# MTB-v2_0_0.net
KiCad netlist of a schematic drawn in EAGLE
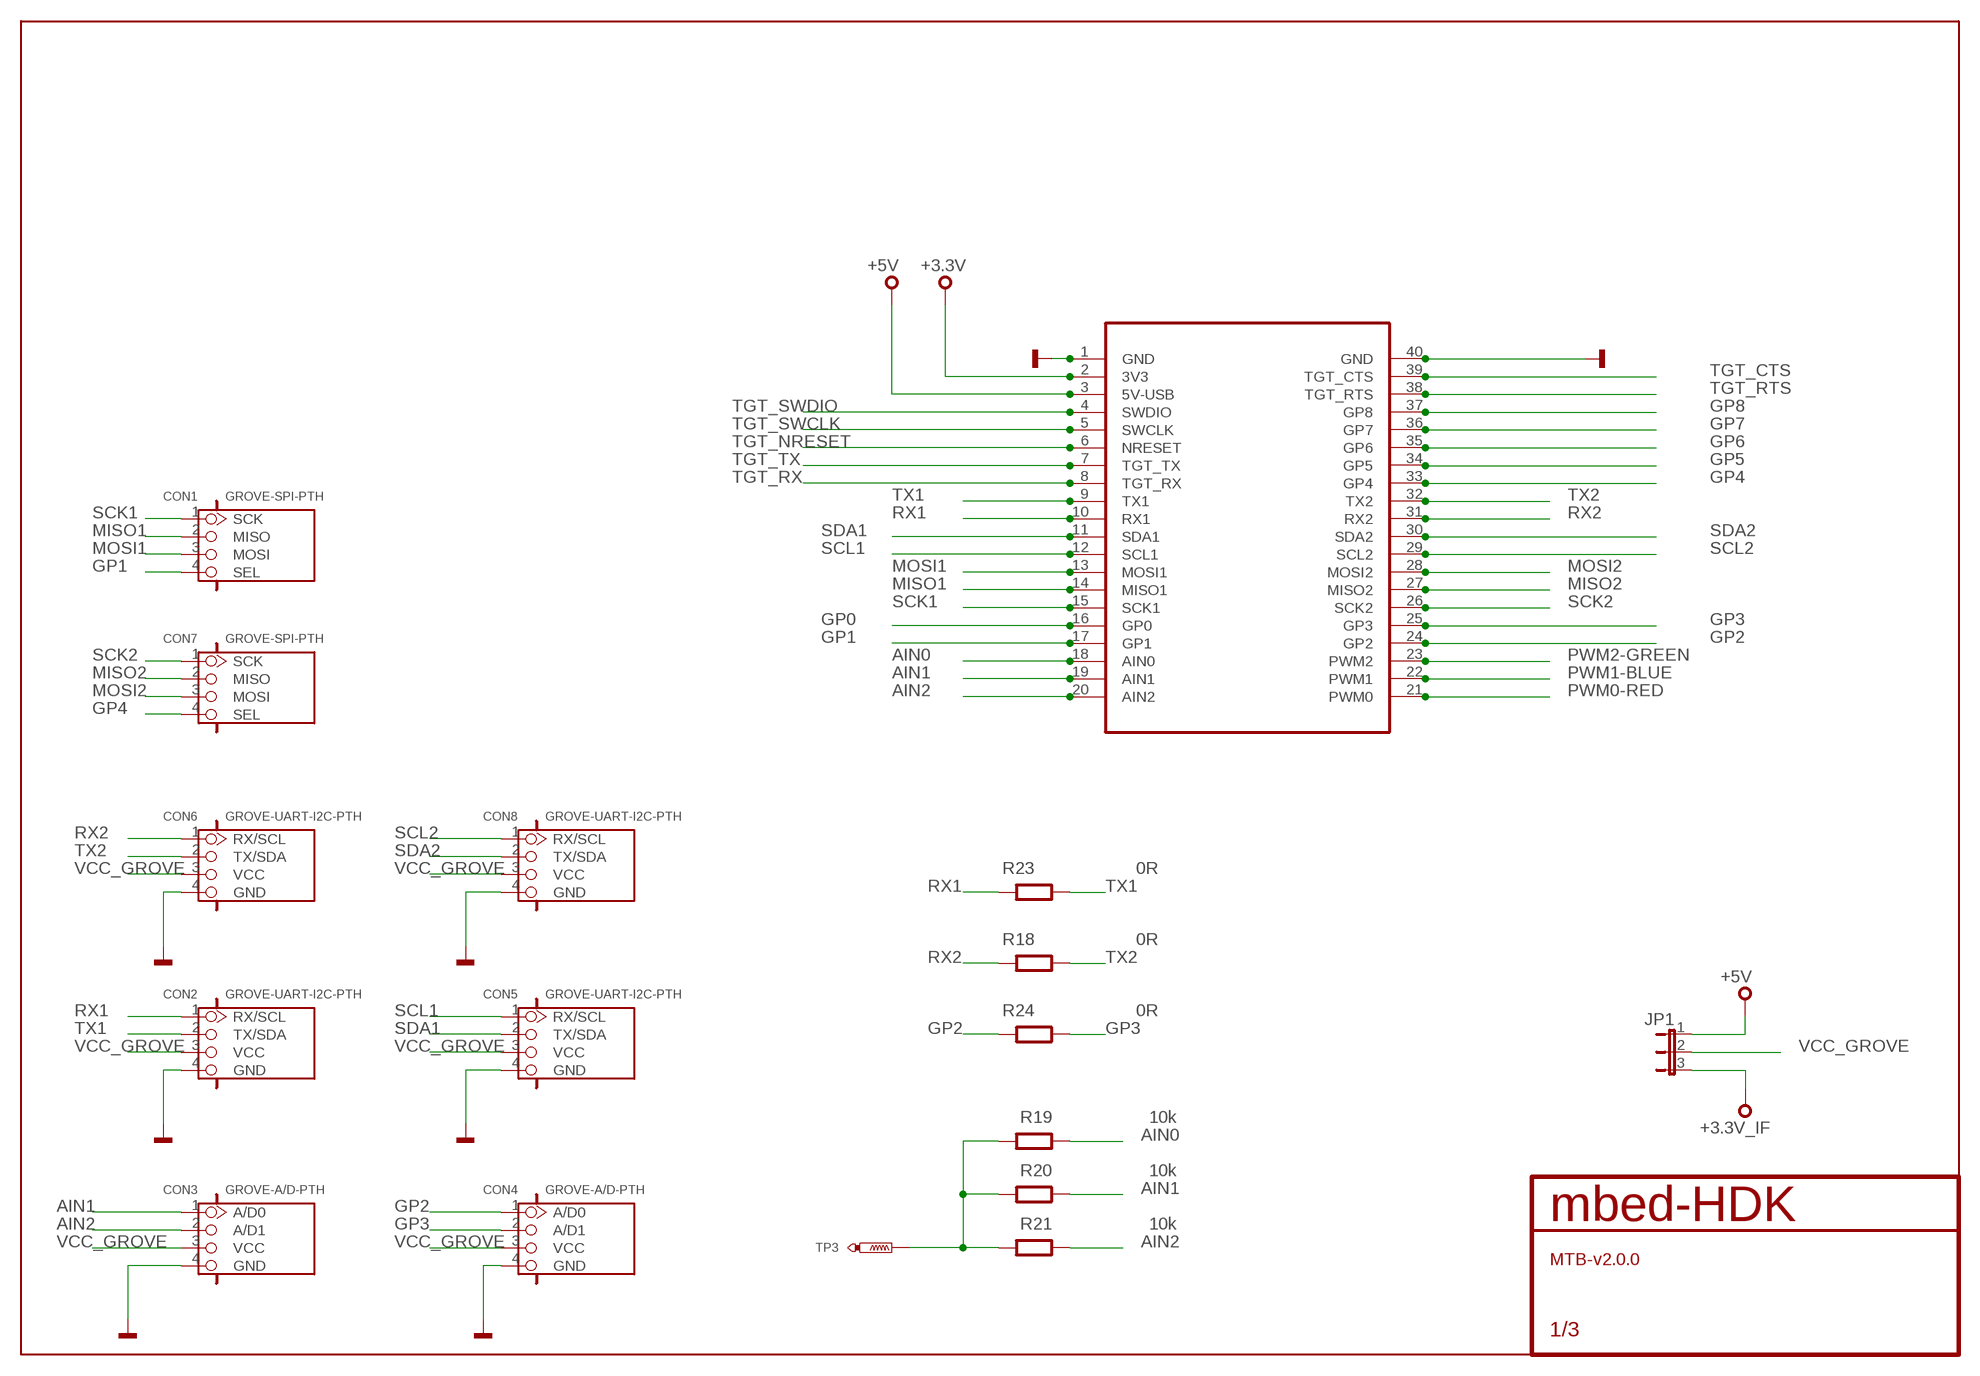
[diagram p0: schematic, sheet 1]
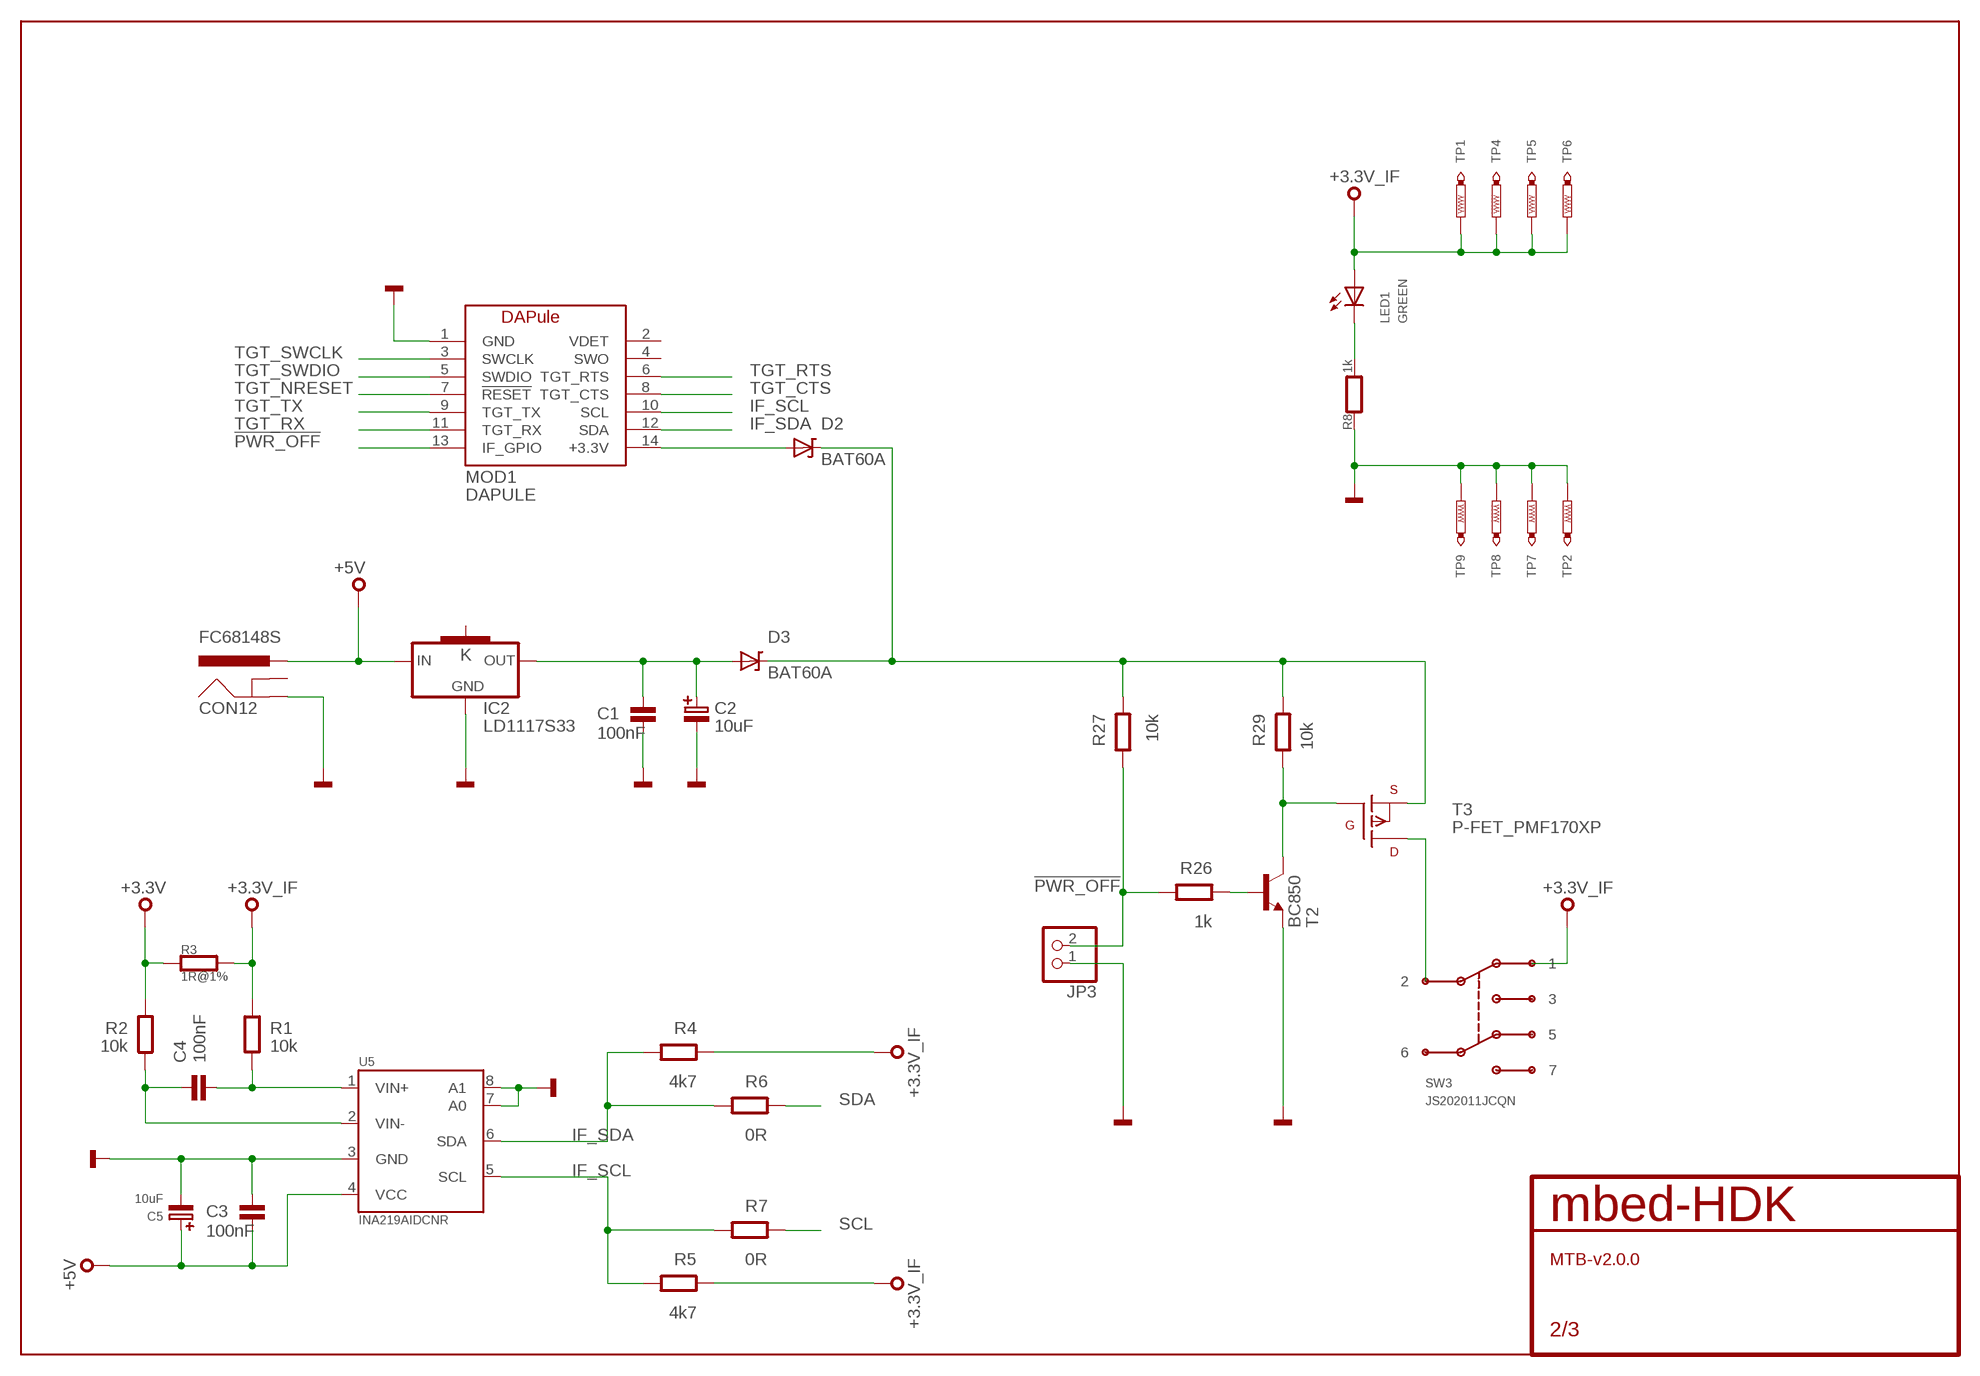
[diagram p1: schematic, sheet 2]
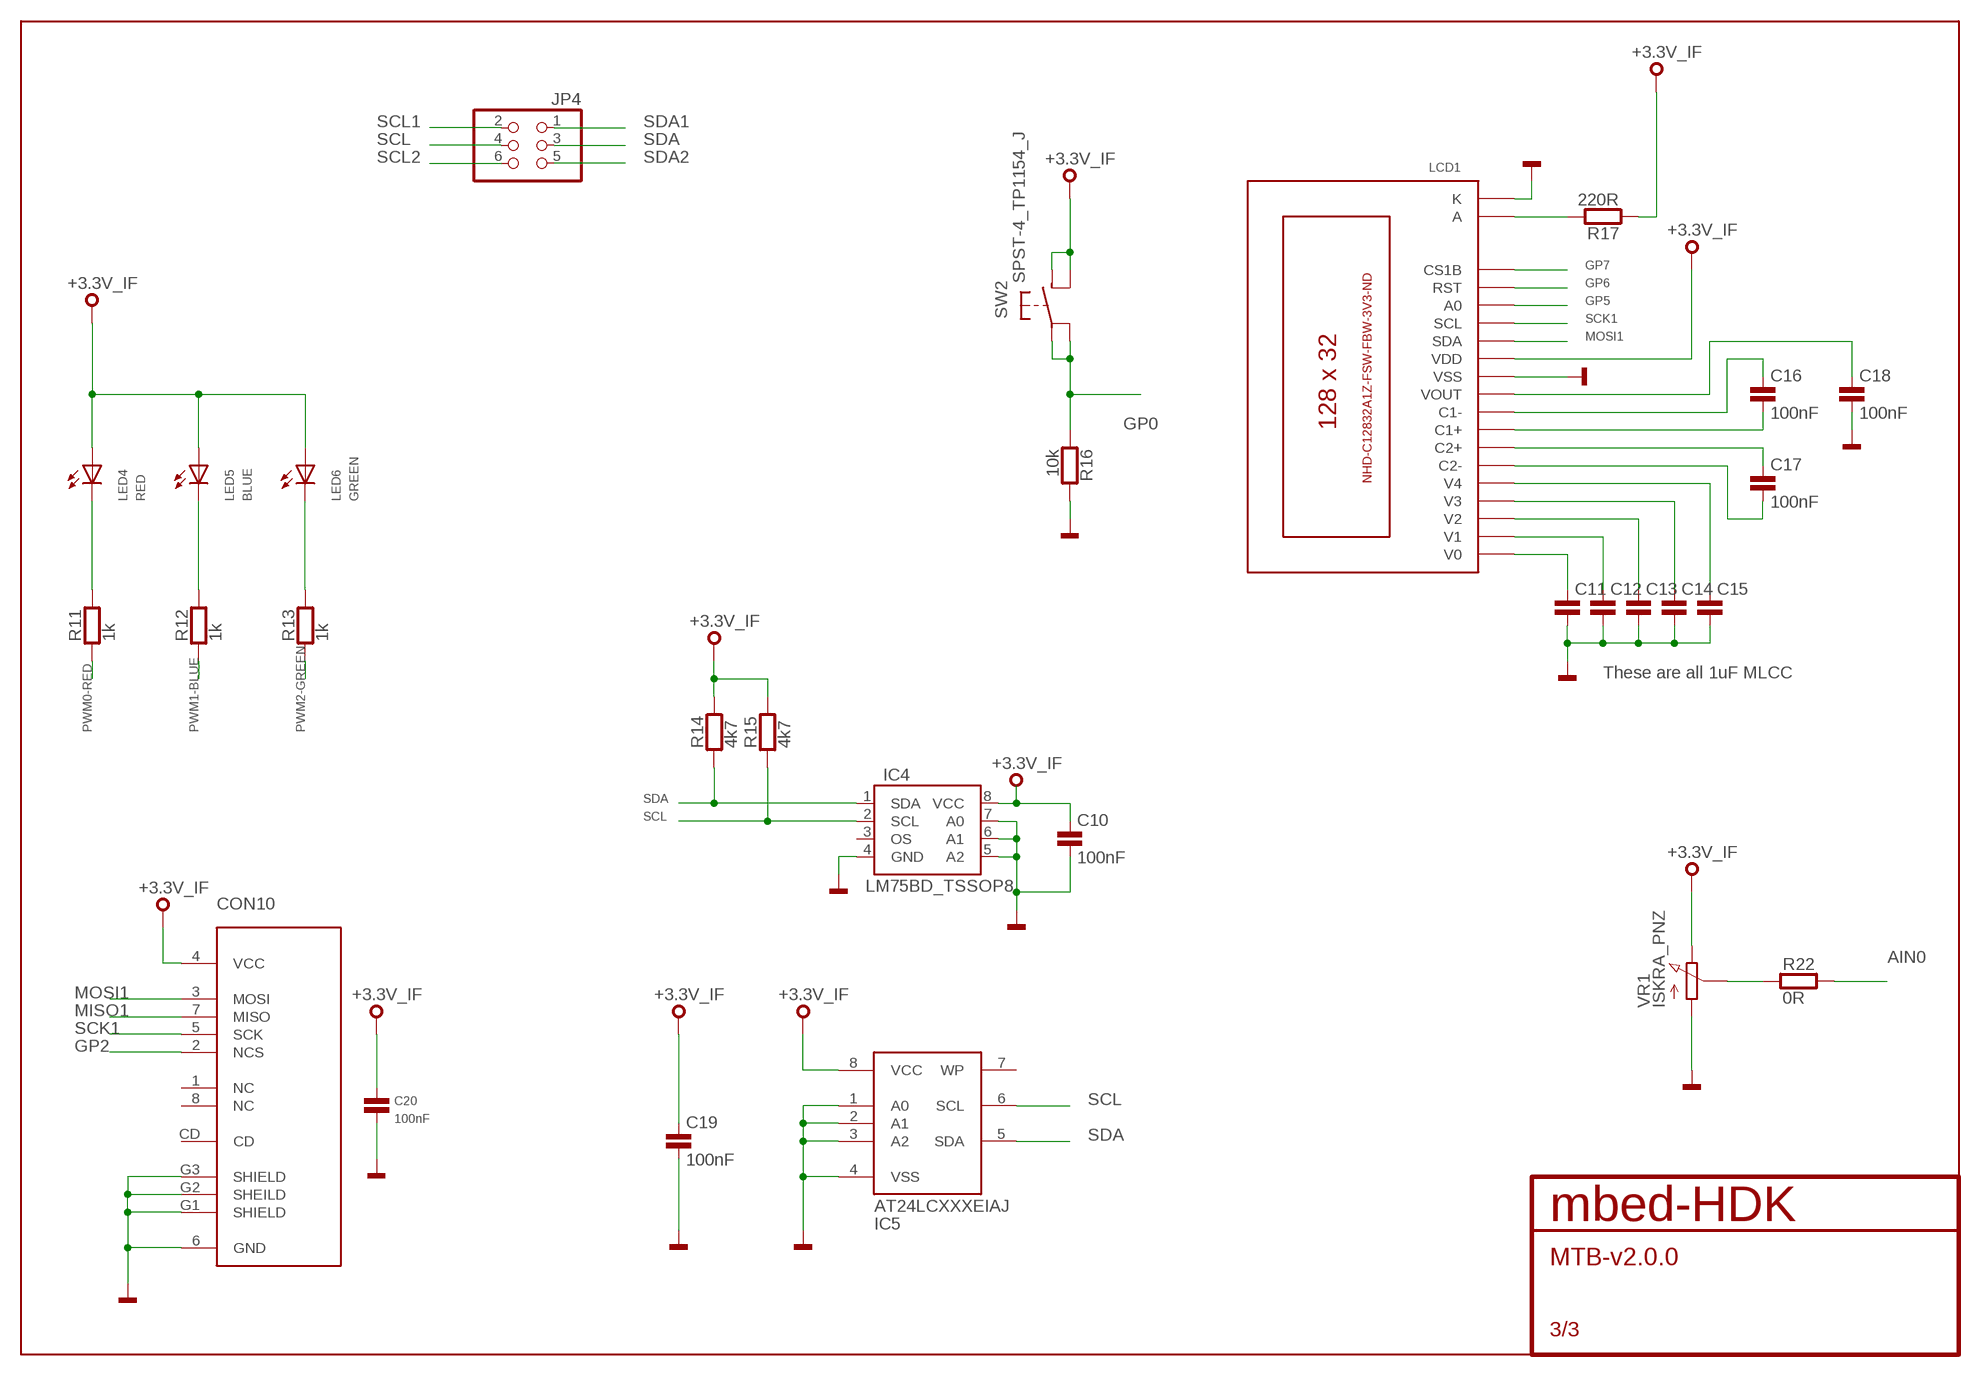
[diagram p2: schematic, sheet 3]

(export (version "E")
  (design (tool "Eeschema 10.0.6"))
  (components
    (comp (ref "CON1")
      (value "GROVE-SPI-PTH")
      (footprint "eagle-import:HW4-2.0")
      (libsource (lib "eagle-import") (part "GROVE-SPI-PTH"))
    )
    (comp (ref "CON2")
      (value "GROVE-UART-I2C-PTH")
      (footprint "eagle-import:HW4-2.0")
      (libsource (lib "eagle-import") (part "GROVE-UART-I2C-PTH"))
    )
    (comp (ref "CON3")
      (value "GROVE-A/D-PTH")
      (footprint "eagle-import:HW4-2.0")
      (libsource (lib "eagle-import") (part "GROVE-A/D-PTH"))
    )
    (comp (ref "CON4")
      (value "GROVE-A/D-PTH")
      (footprint "eagle-import:HW4-2.0")
      (libsource (lib "eagle-import") (part "GROVE-A/D-PTH"))
    )
    (comp (ref "CON5")
      (value "GROVE-UART-I2C-PTH")
      (footprint "eagle-import:HW4-2.0")
      (libsource (lib "eagle-import") (part "GROVE-UART-I2C-PTH"))
    )
    (comp (ref "CON6")
      (value "GROVE-UART-I2C-PTH")
      (footprint "eagle-import:HW4-2.0")
      (libsource (lib "eagle-import") (part "GROVE-UART-I2C-PTH"))
    )
    (comp (ref "CON7")
      (value "GROVE-SPI-PTH")
      (footprint "eagle-import:HW4-2.0")
      (libsource (lib "eagle-import") (part "GROVE-SPI-PTH"))
    )
    (comp (ref "CON8")
      (value "GROVE-UART-I2C-PTH")
      (footprint "eagle-import:HW4-2.0")
      (libsource (lib "eagle-import") (part "GROVE-UART-I2C-PTH"))
    )
    (comp (ref "JP1")
      (value "JP2E")
      (footprint "eagle-import:JP2")
      (libsource (lib "eagle-import") (part "JP2E"))
    )
    (comp (ref "R18")
      (value "0R")
      (footprint "eagle-import:0603@1")
      (libsource (lib "eagle-import") (part "R0603"))
    )
    (comp (ref "R19")
      (value "10k")
      (footprint "eagle-import:0603@1")
      (libsource (lib "eagle-import") (part "R0603"))
    )
    (comp (ref "R20")
      (value "10k")
      (footprint "eagle-import:0603@1")
      (libsource (lib "eagle-import") (part "R0603"))
    )
    (comp (ref "R21")
      (value "10k")
      (footprint "eagle-import:0603@1")
      (libsource (lib "eagle-import") (part "R0603"))
    )
    (comp (ref "R23")
      (value "0R")
      (footprint "eagle-import:0603@1")
      (libsource (lib "eagle-import") (part "R0603"))
    )
    (comp (ref "R24")
      (value "0R")
      (footprint "eagle-import:0603@1")
      (libsource (lib "eagle-import") (part "R0603"))
    )
    (comp (ref "SKT1")
      (value "MODULE_SOCKET")
      (footprint "eagle-import:MODULE_SOCKET")
      (libsource (lib "eagle-import") (part "MODULE_SOCKET"))
    )
    (comp (ref "TP3")
      (value "TEST-POINT-50R-PTH")
      (footprint "eagle-import:TP50-PTH")
      (libsource (lib "eagle-import") (part "TEST-POINT-50R-PTH"))
    )
    (comp (ref "C10")
      (value "100nF")
      (footprint "eagle-import:0603")
      (libsource (lib "eagle-import") (part "mbed-rlcq_C0603"))
    )
    (comp (ref "C11")
      (value "100nF")
      (footprint "eagle-import:0603")
      (libsource (lib "eagle-import") (part "mbed-rlcq_C0603"))
    )
    (comp (ref "C12")
      (value "100nF")
      (footprint "eagle-import:0603")
      (libsource (lib "eagle-import") (part "mbed-rlcq_C0603"))
    )
    (comp (ref "C13")
      (value "100nF")
      (footprint "eagle-import:0603")
      (libsource (lib "eagle-import") (part "mbed-rlcq_C0603"))
    )
    (comp (ref "C14")
      (value "100nF")
      (footprint "eagle-import:0603")
      (libsource (lib "eagle-import") (part "mbed-rlcq_C0603"))
    )
    (comp (ref "C15")
      (value "100nF")
      (footprint "eagle-import:0603")
      (libsource (lib "eagle-import") (part "mbed-rlcq_C0603"))
    )
    (comp (ref "C16")
      (value "100nF")
      (footprint "eagle-import:0603")
      (libsource (lib "eagle-import") (part "mbed-rlcq_C0603"))
    )
    (comp (ref "C17")
      (value "100nF")
      (footprint "eagle-import:0603")
      (libsource (lib "eagle-import") (part "mbed-rlcq_C0603"))
    )
    (comp (ref "C18")
      (value "100nF")
      (footprint "eagle-import:0603")
      (libsource (lib "eagle-import") (part "mbed-rlcq_C0603"))
    )
    (comp (ref "C19")
      (value "100nF")
      (footprint "eagle-import:0603")
      (libsource (lib "eagle-import") (part "mbed-rlcq_C0603"))
    )
    (comp (ref "C20")
      (value "100nF")
      (footprint "eagle-import:0603")
      (libsource (lib "eagle-import") (part "C0603"))
    )
    (comp (ref "CON10")
      (value "MICRO-SD")
      (footprint "eagle-import:AMPHENOL-101-00660-68-6")
      (libsource (lib "eagle-import") (part "MICRO-SD"))
    )
    (comp (ref "IC4")
      (value "LM75BD_TSSOP8")
      (footprint "eagle-import:TSSOP8")
      (libsource (lib "eagle-import") (part "LM75BD_TSSOP8"))
    )
    (comp (ref "IC5")
      (value "AT24LCXXXEIAJ")
      (footprint "eagle-import:SO08-EIAJ")
      (libsource (lib "eagle-import") (part "AT24LCXXXEIAJ"))
    )
    (comp (ref "JP4")
      (value "PINHD-2X3")
      (footprint "eagle-import:2X03")
      (libsource (lib "eagle-import") (part "PINHD-2X3"))
    )
    (comp (ref "LCD1")
      (value "C12832A1Z")
      (footprint "eagle-import:C12832A1Z")
      (libsource (lib "eagle-import") (part "C12832A1Z"))
    )
    (comp (ref "LED4")
      (value "RED")
      (footprint "eagle-import:CHIPLED_0603")
      (libsource (lib "eagle-import") (part "LED0603"))
    )
    (comp (ref "LED5")
      (value "BLUE")
      (footprint "eagle-import:CHIPLED_0603")
      (libsource (lib "eagle-import") (part "LED0603"))
    )
    (comp (ref "LED6")
      (value "GREEN")
      (footprint "eagle-import:CHIPLED_0603")
      (libsource (lib "eagle-import") (part "LED0603"))
    )
    (comp (ref "R11")
      (value "1k")
      (footprint "eagle-import:0603")
      (libsource (lib "eagle-import") (part "mbed-rlcq_R0603"))
    )
    (comp (ref "R12")
      (value "1k")
      (footprint "eagle-import:0603")
      (libsource (lib "eagle-import") (part "mbed-rlcq_R0603"))
    )
    (comp (ref "R13")
      (value "1k")
      (footprint "eagle-import:0603")
      (libsource (lib "eagle-import") (part "mbed-rlcq_R0603"))
    )
    (comp (ref "R14")
      (value "4k7")
      (footprint "eagle-import:0603")
      (libsource (lib "eagle-import") (part "mbed-rlcq_R0603"))
    )
    (comp (ref "R15")
      (value "4k7")
      (footprint "eagle-import:0603")
      (libsource (lib "eagle-import") (part "mbed-rlcq_R0603"))
    )
    (comp (ref "R16")
      (value "10k")
      (footprint "eagle-import:0603")
      (libsource (lib "eagle-import") (part "mbed-rlcq_R0603"))
    )
    (comp (ref "R17")
      (value "220R")
      (footprint "eagle-import:0603")
      (libsource (lib "eagle-import") (part "mbed-rlcq_R0603"))
    )
    (comp (ref "R22")
      (value "0R")
      (footprint "eagle-import:0603")
      (libsource (lib "eagle-import") (part "mbed-rlcq_R0603"))
    )
    (comp (ref "SW2")
      (value "SPST-4_TP1154_J")
      (footprint "eagle-import:TP-1154X")
      (libsource (lib "eagle-import") (part "SPST-4_TP1154_J"))
    )
    (comp (ref "VR1")
      (value "ISKRA_PNZ")
      (footprint "eagle-import:CA14V")
      (libsource (lib "eagle-import") (part "ISKRA_PNZ"))
    )
    (comp (ref "C1")
      (value "100nF")
      (footprint "eagle-import:0603")
      (libsource (lib "eagle-import") (part "C0603"))
    )
    (comp (ref "C2")
      (value "10uF")
      (footprint "eagle-import:SMC_B")
      (libsource (lib "eagle-import") (part "C-POLB"))
    )
    (comp (ref "C3")
      (value "100nF")
      (footprint "eagle-import:0603")
      (libsource (lib "eagle-import") (part "C0603"))
    )
    (comp (ref "C4")
      (value "100nF")
      (footprint "eagle-import:0603")
      (libsource (lib "eagle-import") (part "C0603"))
    )
    (comp (ref "C5")
      (value "10uF")
      (footprint "eagle-import:SMC_A")
      (libsource (lib "eagle-import") (part "mbed-HDK-RLC_C-POLA"))
    )
    (comp (ref "CON12")
      (value "FC68148S")
      (footprint "eagle-import:FC68148S")
      (libsource (lib "eagle-import") (part "FC68148S"))
    )
    (comp (ref "D2")
      (value "BAT60A")
      (footprint "eagle-import:SOD323")
      (fields (field (name "MF") "Infineon"))
      (libsource (lib "eagle-import") (part "BAT60A"))
    )
    (comp (ref "D3")
      (value "BAT60A")
      (footprint "eagle-import:SOD323")
      (fields (field (name "MF") "Infineon"))
      (libsource (lib "eagle-import") (part "BAT60A"))
    )
    (comp (ref "IC2")
      (value "LD1117S33")
      (footprint "eagle-import:SOT223")
      (libsource (lib "eagle-import") (part "LD1117S33"))
    )
    (comp (ref "JP3")
      (value "PINHD-1X2")
      (footprint "eagle-import:1X02")
      (libsource (lib "eagle-import") (part "PINHD-1X2"))
    )
    (comp (ref "LED1")
      (value "GREEN")
      (footprint "eagle-import:CHIPLED_0603")
      (fields (field (name "MF") "Wurth Electronics Inc"))
      (libsource (lib "eagle-import") (part "SMD_LED0603"))
    )
    (comp (ref "MOD1")
      (value "DAPULE")
      (footprint "eagle-import:DAPULE")
      (libsource (lib "eagle-import") (part "DAPULE"))
    )
    (comp (ref "R1")
      (value "10k")
      (footprint "eagle-import:0603@1")
      (libsource (lib "eagle-import") (part "R0603"))
    )
    (comp (ref "R2")
      (value "10k")
      (footprint "eagle-import:0603@1")
      (libsource (lib "eagle-import") (part "R0603"))
    )
    (comp (ref "R3")
      (value "1R@1%")
      (footprint "eagle-import:0603")
      (libsource (lib "eagle-import") (part "mbed-HDK-RLC_R0603"))
    )
    (comp (ref "R4")
      (value "4k7")
      (footprint "eagle-import:0603@1")
      (libsource (lib "eagle-import") (part "R0603"))
    )
    (comp (ref "R5")
      (value "4k7")
      (footprint "eagle-import:0603@1")
      (libsource (lib "eagle-import") (part "R0603"))
    )
    (comp (ref "R6")
      (value "0R")
      (footprint "eagle-import:0603@1")
      (libsource (lib "eagle-import") (part "R0603"))
    )
    (comp (ref "R7")
      (value "0R")
      (footprint "eagle-import:0603@1")
      (libsource (lib "eagle-import") (part "R0603"))
    )
    (comp (ref "R8")
      (value "1k")
      (footprint "eagle-import:0603")
      (libsource (lib "eagle-import") (part "RESISTOR0603"))
    )
    (comp (ref "R26")
      (value "1k")
      (footprint "eagle-import:0603@1")
      (libsource (lib "eagle-import") (part "R0603"))
    )
    (comp (ref "R27")
      (value "10k")
      (footprint "eagle-import:0603@1")
      (libsource (lib "eagle-import") (part "R0603"))
    )
    (comp (ref "R29")
      (value "10k")
      (footprint "eagle-import:0603@1")
      (libsource (lib "eagle-import") (part "R0603"))
    )
    (comp (ref "SW3")
      (value "JS202011JCQN")
      (footprint "eagle-import:JS202011JCQN")
      (fields (field (name "MF") "C&K Components"))
      (libsource (lib "eagle-import") (part "JS202011JCQN"))
    )
    (comp (ref "T2")
      (value "BC850")
      (footprint "eagle-import:SOT23")
      (libsource (lib "eagle-import") (part "BC850"))
    )
    (comp (ref "T3")
      (value "P-FET_PMF170XP")
      (footprint "eagle-import:SOT23-BEC")
      (libsource (lib "eagle-import") (part "P-FET_PMF170XP"))
    )
    (comp (ref "TP1")
      (value "TEST-POINT-50R-PTH")
      (footprint "eagle-import:TP50-PTH")
      (libsource (lib "eagle-import") (part "TEST-POINT-50R-PTH"))
    )
    (comp (ref "TP2")
      (value "TEST-POINT-50R-PTH")
      (footprint "eagle-import:TP50-PTH")
      (libsource (lib "eagle-import") (part "TEST-POINT-50R-PTH"))
    )
    (comp (ref "TP4")
      (value "TEST-POINT-50R-PTH")
      (footprint "eagle-import:TP50-PTH")
      (libsource (lib "eagle-import") (part "TEST-POINT-50R-PTH"))
    )
    (comp (ref "TP5")
      (value "TEST-POINT-50R-PTH")
      (footprint "eagle-import:TP50-PTH")
      (libsource (lib "eagle-import") (part "TEST-POINT-50R-PTH"))
    )
    (comp (ref "TP6")
      (value "TEST-POINT-50R-PTH")
      (footprint "eagle-import:TP50-PTH")
      (libsource (lib "eagle-import") (part "TEST-POINT-50R-PTH"))
    )
    (comp (ref "TP7")
      (value "TEST-POINT-50R-PTH")
      (footprint "eagle-import:TP50-PTH")
      (libsource (lib "eagle-import") (part "TEST-POINT-50R-PTH"))
    )
    (comp (ref "TP8")
      (value "TEST-POINT-50R-PTH")
      (footprint "eagle-import:TP50-PTH")
      (libsource (lib "eagle-import") (part "TEST-POINT-50R-PTH"))
    )
    (comp (ref "TP9")
      (value "TEST-POINT-50R-PTH")
      (footprint "eagle-import:TP50-PTH")
      (libsource (lib "eagle-import") (part "TEST-POINT-50R-PTH"))
    )
    (comp (ref "U5")
      (value "INA219AIDCNR")
      (footprint "eagle-import:SOT23-8")
      (fields (field (name "MF") "Texas Instruments"))
      (libsource (lib "eagle-import") (part "INA219AIDCNR"))
    )
  )
  (nets
    (net (code "1") (name "+3.3V") (class "Default")
      (node (ref "R2") (pin "2") (pinfunction "P$2_2") (pintype "passive"))
      (node (ref "R3") (pin "1") (pinfunction "P$1_1") (pintype "passive"))
      (node (ref "SKT1") (pin "2") (pinfunction "3V3_2") (pintype "bidirectional"))
      (node (ref "SKT1") (pin "P$42") (pinfunction "P$42_P$42") (pintype "bidirectional"))
    )
    (net (code "2") (name "+3.3V_IF") (class "Default")
      (node (ref "C10") (pin "1") (pinfunction "P$1_1") (pintype "passive"))
      (node (ref "C19") (pin "1") (pinfunction "P$1_1") (pintype "passive"))
      (node (ref "C20") (pin "1") (pinfunction "P$1_1") (pintype "passive"))
      (node (ref "CON10") (pin "4") (pinfunction "VCC_4") (pintype "bidirectional"))
      (node (ref "IC4") (pin "8") (pinfunction "VCC_8") (pintype "bidirectional"))
      (node (ref "IC5") (pin "8") (pinfunction "VCC_8") (pintype "power_in"))
      (node (ref "JP1") (pin "3") (pinfunction "3_3") (pintype "passive"))
      (node (ref "LCD1") (pin "P$12") (pinfunction "VDD_P$12") (pintype "bidirectional"))
      (node (ref "LED1") (pin "A") (pinfunction "A_A") (pintype "passive"))
      (node (ref "LED4") (pin "A") (pinfunction "A_A") (pintype "passive"))
      (node (ref "LED5") (pin "A") (pinfunction "A_A") (pintype "passive"))
      (node (ref "LED6") (pin "A") (pinfunction "A_A") (pintype "passive"))
      (node (ref "R1") (pin "2") (pinfunction "P$2_2") (pintype "passive"))
      (node (ref "R14") (pin "2") (pinfunction "P$2_2") (pintype "passive"))
      (node (ref "R15") (pin "2") (pinfunction "P$2_2") (pintype "passive"))
      (node (ref "R17") (pin "1") (pinfunction "P$1_1") (pintype "passive"))
      (node (ref "R3") (pin "2") (pinfunction "P$2_2") (pintype "passive"))
      (node (ref "R4") (pin "1") (pinfunction "P$1_1") (pintype "passive"))
      (node (ref "R5") (pin "1") (pinfunction "P$1_1") (pintype "passive"))
      (node (ref "SW2") (pin "B1") (pinfunction "B1_B1") (pintype "passive"))
      (node (ref "SW2") (pin "B2") (pinfunction "B2_B2") (pintype "passive"))
      (node (ref "SW3") (pin "1") (pinfunction "1_1") (pintype "bidirectional"))
      (node (ref "TP1") (pin "TP") (pinfunction "TP_TP") (pintype "input"))
      (node (ref "TP4") (pin "TP") (pinfunction "TP_TP") (pintype "input"))
      (node (ref "TP5") (pin "TP") (pinfunction "TP_TP") (pintype "input"))
      (node (ref "TP6") (pin "TP") (pinfunction "TP_TP") (pintype "input"))
      (node (ref "VR1") (pin "P$3") (pinfunction "E_P$3") (pintype "passive"))
    )
    (net (code "3") (name "+5V") (class "Default")
      (node (ref "C3") (pin "2") (pinfunction "P$2_2") (pintype "passive"))
      (node (ref "C5") (pin "+") (pinfunction "+_+") (pintype "passive"))
      (node (ref "CON12") (pin "1-1") (pinfunction "PWR_1-1") (pintype "bidirectional"))
      (node (ref "CON12") (pin "1-2") (pinfunction "PWR_1-2") (pintype "bidirectional"))
      (node (ref "IC2") (pin "3") (pinfunction "IN_3") (pintype "input"))
      (node (ref "JP1") (pin "1") (pinfunction "1_1") (pintype "passive"))
      (node (ref "SKT1") (pin "3") (pinfunction "5V-USB_3") (pintype "bidirectional"))
      (node (ref "SKT1") (pin "P$43") (pinfunction "P$43_P$43") (pintype "bidirectional"))
      (node (ref "U5") (pin "4") (pinfunction "VCC_4") (pintype "power_in"))
    )
    (net (code "4") (name "AIN0") (class "Default")
      (node (ref "R19") (pin "1") (pinfunction "P$1_1") (pintype "passive"))
      (node (ref "R22") (pin "2") (pinfunction "P$2_2") (pintype "passive"))
      (node (ref "SKT1") (pin "18") (pinfunction "AIN0_18") (pintype "bidirectional"))
      (node (ref "SKT1") (pin "P$58") (pinfunction "P$58_P$58") (pintype "bidirectional"))
    )
    (net (code "5") (name "AIN1") (class "Default")
      (node (ref "CON3") (pin "1") (pinfunction "A/D0_1") (pintype "bidirectional"))
      (node (ref "R20") (pin "1") (pinfunction "P$1_1") (pintype "passive"))
      (node (ref "SKT1") (pin "19") (pinfunction "AIN1_19") (pintype "bidirectional"))
      (node (ref "SKT1") (pin "P$59") (pinfunction "P$59_P$59") (pintype "bidirectional"))
    )
    (net (code "6") (name "AIN2") (class "Default")
      (node (ref "CON3") (pin "2") (pinfunction "A/D1_2") (pintype "bidirectional"))
      (node (ref "R21") (pin "1") (pinfunction "P$1_1") (pintype "passive"))
      (node (ref "SKT1") (pin "20") (pinfunction "AIN2_20") (pintype "bidirectional"))
      (node (ref "SKT1") (pin "P$60") (pinfunction "P$60_P$60") (pintype "bidirectional"))
    )
    (net (code "7") (name "GND") (class "Default")
      (node (ref "C1") (pin "2") (pinfunction "P$2_2") (pintype "passive"))
      (node (ref "C10") (pin "2") (pinfunction "P$2_2") (pintype "passive"))
      (node (ref "C11") (pin "2") (pinfunction "P$2_2") (pintype "passive"))
      (node (ref "C12") (pin "2") (pinfunction "P$2_2") (pintype "passive"))
      (node (ref "C13") (pin "2") (pinfunction "P$2_2") (pintype "passive"))
      (node (ref "C14") (pin "2") (pinfunction "P$2_2") (pintype "passive"))
      (node (ref "C15") (pin "2") (pinfunction "P$2_2") (pintype "passive"))
      (node (ref "C18") (pin "2") (pinfunction "P$2_2") (pintype "passive"))
      (node (ref "C19") (pin "2") (pinfunction "P$2_2") (pintype "passive"))
      (node (ref "C2") (pin "-") (pinfunction "-_-") (pintype "passive"))
      (node (ref "C20") (pin "2") (pinfunction "P$2_2") (pintype "passive"))
      (node (ref "C3") (pin "1") (pinfunction "P$1_1") (pintype "passive"))
      (node (ref "C5") (pin "-") (pinfunction "-_-") (pintype "passive"))
      (node (ref "CON10") (pin "6") (pinfunction "GND_6") (pintype "bidirectional"))
      (node (ref "CON10") (pin "G1") (pinfunction "SHIELD_G1") (pintype "bidirectional"))
      (node (ref "CON10") (pin "G2") (pinfunction "SHEILD_G2") (pintype "bidirectional"))
      (node (ref "CON10") (pin "G3") (pinfunction "SHIELD_G3") (pintype "bidirectional"))
      (node (ref "CON12") (pin "3") (pinfunction "GND_3") (pintype "bidirectional"))
      (node (ref "CON2") (pin "4") (pinfunction "GND_4") (pintype "bidirectional"))
      (node (ref "CON3") (pin "4") (pinfunction "GND_4") (pintype "bidirectional"))
      (node (ref "CON4") (pin "4") (pinfunction "GND_4") (pintype "bidirectional"))
      (node (ref "CON5") (pin "4") (pinfunction "GND_4") (pintype "bidirectional"))
      (node (ref "CON6") (pin "4") (pinfunction "GND_4") (pintype "bidirectional"))
      (node (ref "CON8") (pin "4") (pinfunction "GND_4") (pintype "bidirectional"))
      (node (ref "IC2") (pin "1") (pinfunction "GND_1") (pintype "input"))
      (node (ref "IC4") (pin "4") (pinfunction "GND_4") (pintype "bidirectional"))
      (node (ref "IC4") (pin "5") (pinfunction "A2_5") (pintype "bidirectional"))
      (node (ref "IC4") (pin "6") (pinfunction "A1_6") (pintype "bidirectional"))
      (node (ref "IC4") (pin "7") (pinfunction "A0_7") (pintype "bidirectional"))
      (node (ref "IC5") (pin "1") (pinfunction "A0_1") (pintype "bidirectional"))
      (node (ref "IC5") (pin "2") (pinfunction "A1_2") (pintype "bidirectional"))
      (node (ref "IC5") (pin "3") (pinfunction "A2_3") (pintype "bidirectional"))
      (node (ref "IC5") (pin "4") (pinfunction "VSS_4") (pintype "power_in"))
      (node (ref "JP3") (pin "1") (pinfunction "1_1") (pintype "passive"))
      (node (ref "LCD1") (pin "K") (pinfunction "K_K") (pintype "bidirectional"))
      (node (ref "LCD1") (pin "P$11") (pinfunction "VSS_P$11") (pintype "bidirectional"))
      (node (ref "MOD1") (pin "1") (pinfunction "GND_1") (pintype "bidirectional"))
      (node (ref "R16") (pin "2") (pinfunction "P$2_2") (pintype "passive"))
      (node (ref "R8") (pin "1") (pinfunction "P$1_1") (pintype "passive"))
      (node (ref "SKT1") (pin "1") (pinfunction "GND_1") (pintype "bidirectional"))
      (node (ref "SKT1") (pin "40") (pinfunction "GND_40") (pintype "bidirectional"))
      (node (ref "SKT1") (pin "P$41") (pinfunction "P$41_P$41") (pintype "bidirectional"))
      (node (ref "SKT1") (pin "P$80") (pinfunction "P$80_P$80") (pintype "bidirectional"))
      (node (ref "T2") (pin "2") (pinfunction "E_2") (pintype "passive"))
      (node (ref "TP2") (pin "TP") (pinfunction "TP_TP") (pintype "input"))
      (node (ref "TP7") (pin "TP") (pinfunction "TP_TP") (pintype "input"))
      (node (ref "TP8") (pin "TP") (pinfunction "TP_TP") (pintype "input"))
      (node (ref "TP9") (pin "TP") (pinfunction "TP_TP") (pintype "input"))
      (node (ref "U5") (pin "3") (pinfunction "GND_3") (pintype "power_in"))
      (node (ref "U5") (pin "7") (pinfunction "A0_7") (pintype "input"))
      (node (ref "U5") (pin "8") (pinfunction "A1_8") (pintype "input"))
      (node (ref "VR1") (pin "P$1") (pinfunction "A_P$1") (pintype "passive"))
    )
    (net (code "8") (name "GP0") (class "Default")
      (node (ref "R16") (pin "1") (pinfunction "P$1_1") (pintype "passive"))
      (node (ref "SKT1") (pin "16") (pinfunction "GP0_16") (pintype "bidirectional"))
      (node (ref "SKT1") (pin "P$56") (pinfunction "P$56_P$56") (pintype "bidirectional"))
      (node (ref "SW2") (pin "A1") (pinfunction "A1_A1") (pintype "passive"))
      (node (ref "SW2") (pin "A2") (pinfunction "A2_A2") (pintype "passive"))
    )
    (net (code "9") (name "GP1") (class "Default")
      (node (ref "CON1") (pin "4") (pinfunction "SEL_4") (pintype "bidirectional"))
      (node (ref "SKT1") (pin "17") (pinfunction "GP1_17") (pintype "bidirectional"))
      (node (ref "SKT1") (pin "P$57") (pinfunction "P$57_P$57") (pintype "bidirectional"))
    )
    (net (code "10") (name "GP2") (class "Default")
      (node (ref "CON10") (pin "2") (pinfunction "NCS_2") (pintype "bidirectional"))
      (node (ref "CON4") (pin "1") (pinfunction "A/D0_1") (pintype "bidirectional"))
      (node (ref "R24") (pin "2") (pinfunction "P$2_2") (pintype "passive"))
      (node (ref "SKT1") (pin "24") (pinfunction "GP2_24") (pintype "bidirectional"))
      (node (ref "SKT1") (pin "P$64") (pinfunction "P$64_P$64") (pintype "bidirectional"))
    )
    (net (code "11") (name "GP3") (class "Default")
      (node (ref "CON4") (pin "2") (pinfunction "A/D1_2") (pintype "bidirectional"))
      (node (ref "R24") (pin "1") (pinfunction "P$1_1") (pintype "passive"))
      (node (ref "SKT1") (pin "25") (pinfunction "GP3_25") (pintype "bidirectional"))
      (node (ref "SKT1") (pin "P$65") (pinfunction "P$65_P$65") (pintype "bidirectional"))
    )
    (net (code "12") (name "GP4") (class "Default")
      (node (ref "CON7") (pin "4") (pinfunction "SEL_4") (pintype "bidirectional"))
      (node (ref "SKT1") (pin "33") (pinfunction "GP4_33") (pintype "bidirectional"))
      (node (ref "SKT1") (pin "P$73") (pinfunction "P$73_P$73") (pintype "bidirectional"))
    )
    (net (code "13") (name "GP5") (class "Default")
      (node (ref "LCD1") (pin "P$15") (pinfunction "A0_P$15") (pintype "bidirectional"))
      (node (ref "SKT1") (pin "34") (pinfunction "GP5_34") (pintype "bidirectional"))
      (node (ref "SKT1") (pin "P$74") (pinfunction "P$74_P$74") (pintype "bidirectional"))
    )
    (net (code "14") (name "GP6") (class "Default")
      (node (ref "LCD1") (pin "P$16") (pinfunction "RST_P$16") (pintype "bidirectional"))
      (node (ref "SKT1") (pin "35") (pinfunction "GP6_35") (pintype "bidirectional"))
      (node (ref "SKT1") (pin "P$75") (pinfunction "P$75_P$75") (pintype "bidirectional"))
    )
    (net (code "15") (name "GP7") (class "Default")
      (node (ref "LCD1") (pin "P$17") (pinfunction "CS1B_P$17") (pintype "bidirectional"))
      (node (ref "SKT1") (pin "36") (pinfunction "GP7_36") (pintype "bidirectional"))
      (node (ref "SKT1") (pin "P$76") (pinfunction "P$76_P$76") (pintype "bidirectional"))
    )
    (net (code "16") (name "GP8") (class "Default")
      (node (ref "SKT1") (pin "37") (pinfunction "GP8_37") (pintype "bidirectional"))
      (node (ref "SKT1") (pin "P$77") (pinfunction "P$77_P$77") (pintype "bidirectional"))
    )
    (net (code "17") (name "IF_SCL") (class "Default")
      (node (ref "MOD1") (pin "10") (pinfunction "SCL_10") (pintype "bidirectional"))
      (node (ref "R5") (pin "2") (pinfunction "P$2_2") (pintype "passive"))
      (node (ref "R7") (pin "2") (pinfunction "P$2_2") (pintype "passive"))
      (node (ref "U5") (pin "5") (pinfunction "SCL_5") (pintype "bidirectional"))
    )
    (net (code "18") (name "IF_SDA") (class "Default")
      (node (ref "MOD1") (pin "12") (pinfunction "SDA_12") (pintype "bidirectional"))
      (node (ref "R4") (pin "2") (pinfunction "P$2_2") (pintype "passive"))
      (node (ref "R6") (pin "2") (pinfunction "P$2_2") (pintype "passive"))
      (node (ref "U5") (pin "6") (pinfunction "SDA_6") (pintype "bidirectional"))
    )
    (net (code "19") (name "MISO1") (class "Default")
      (node (ref "CON1") (pin "2") (pinfunction "MISO_2") (pintype "bidirectional"))
      (node (ref "CON10") (pin "7") (pinfunction "MISO_7") (pintype "bidirectional"))
      (node (ref "SKT1") (pin "14") (pinfunction "MISO1_14") (pintype "bidirectional"))
      (node (ref "SKT1") (pin "P$54") (pinfunction "P$54_P$54") (pintype "bidirectional"))
    )
    (net (code "20") (name "MISO2") (class "Default")
      (node (ref "CON7") (pin "2") (pinfunction "MISO_2") (pintype "bidirectional"))
      (node (ref "SKT1") (pin "27") (pinfunction "MISO2_27") (pintype "bidirectional"))
      (node (ref "SKT1") (pin "P$67") (pinfunction "P$67_P$67") (pintype "bidirectional"))
    )
    (net (code "21") (name "MOSI1") (class "Default")
      (node (ref "CON1") (pin "3") (pinfunction "MOSI_3") (pintype "bidirectional"))
      (node (ref "CON10") (pin "3") (pinfunction "MOSI_3") (pintype "bidirectional"))
      (node (ref "LCD1") (pin "P$13") (pinfunction "SDA_P$13") (pintype "bidirectional"))
      (node (ref "SKT1") (pin "13") (pinfunction "MOSI1_13") (pintype "bidirectional"))
      (node (ref "SKT1") (pin "P$53") (pinfunction "P$53_P$53") (pintype "bidirectional"))
    )
    (net (code "22") (name "MOSI2") (class "Default")
      (node (ref "CON7") (pin "3") (pinfunction "MOSI_3") (pintype "bidirectional"))
      (node (ref "SKT1") (pin "28") (pinfunction "MOSI2_28") (pintype "bidirectional"))
      (node (ref "SKT1") (pin "P$68") (pinfunction "P$68_P$68") (pintype "bidirectional"))
    )
    (net (code "23") (name "Net-(C1-P$1)") (class "Default")
      (node (ref "C1") (pin "1") (pinfunction "P$1_1") (pintype "passive"))
      (node (ref "C2") (pin "+") (pinfunction "+_+") (pintype "passive"))
      (node (ref "D3") (pin "A") (pinfunction "A_A") (pintype "passive"))
      (node (ref "IC2") (pin "2") (pinfunction "OUT_2") (pintype "passive"))
    )
    (net (code "24") (name "Net-(C4-P$1)") (class "Default")
      (node (ref "C4") (pin "1") (pinfunction "P$1_1") (pintype "passive"))
      (node (ref "R1") (pin "1") (pinfunction "P$1_1") (pintype "passive"))
      (node (ref "U5") (pin "1") (pinfunction "VIN+_1") (pintype "input"))
    )
    (net (code "25") (name "Net-(C4-P$2)") (class "Default")
      (node (ref "C4") (pin "2") (pinfunction "P$2_2") (pintype "passive"))
      (node (ref "R2") (pin "1") (pinfunction "P$1_1") (pintype "passive"))
      (node (ref "U5") (pin "2") (pinfunction "VIN-_2") (pintype "input"))
    )
    (net (code "26") (name "Net-(C11-P$1)") (class "Default")
      (node (ref "C11") (pin "1") (pinfunction "P$1_1") (pintype "passive"))
      (node (ref "LCD1") (pin "P$1") (pinfunction "V0_P$1") (pintype "bidirectional"))
    )
    (net (code "27") (name "Net-(C12-P$1)") (class "Default")
      (node (ref "C12") (pin "1") (pinfunction "P$1_1") (pintype "passive"))
      (node (ref "LCD1") (pin "P$2") (pinfunction "V1_P$2") (pintype "bidirectional"))
    )
    (net (code "28") (name "Net-(C13-P$1)") (class "Default")
      (node (ref "C13") (pin "1") (pinfunction "P$1_1") (pintype "passive"))
      (node (ref "LCD1") (pin "P$3") (pinfunction "V2_P$3") (pintype "bidirectional"))
    )
    (net (code "29") (name "Net-(C14-P$1)") (class "Default")
      (node (ref "C14") (pin "1") (pinfunction "P$1_1") (pintype "passive"))
      (node (ref "LCD1") (pin "P$4") (pinfunction "V3_P$4") (pintype "bidirectional"))
    )
    (net (code "30") (name "Net-(C15-P$1)") (class "Default")
      (node (ref "C15") (pin "1") (pinfunction "P$1_1") (pintype "passive"))
      (node (ref "LCD1") (pin "P$5") (pinfunction "V4_P$5") (pintype "bidirectional"))
    )
    (net (code "31") (name "Net-(C16-P$1)") (class "Default")
      (node (ref "C16") (pin "1") (pinfunction "P$1_1") (pintype "passive"))
      (node (ref "LCD1") (pin "P$9") (pinfunction "C1-_P$9") (pintype "bidirectional"))
    )
    (net (code "32") (name "Net-(C16-P$2)") (class "Default")
      (node (ref "C16") (pin "2") (pinfunction "P$2_2") (pintype "passive"))
      (node (ref "LCD1") (pin "P$8") (pinfunction "C1+_P$8") (pintype "bidirectional"))
    )
    (net (code "33") (name "Net-(C17-P$1)") (class "Default")
      (node (ref "C17") (pin "1") (pinfunction "P$1_1") (pintype "passive"))
      (node (ref "LCD1") (pin "P$7") (pinfunction "C2+_P$7") (pintype "bidirectional"))
    )
    (net (code "34") (name "Net-(C17-P$2)") (class "Default")
      (node (ref "C17") (pin "2") (pinfunction "P$2_2") (pintype "passive"))
      (node (ref "LCD1") (pin "P$6") (pinfunction "C2-_P$6") (pintype "bidirectional"))
    )
    (net (code "35") (name "Net-(C18-P$1)") (class "Default")
      (node (ref "C18") (pin "1") (pinfunction "P$1_1") (pintype "passive"))
      (node (ref "LCD1") (pin "P$10") (pinfunction "VOUT_P$10") (pintype "bidirectional"))
    )
    (net (code "36") (name "Net-(MOD1-+3.3V)") (class "Default")
      (node (ref "D2") (pin "A") (pinfunction "A_A") (pintype "passive"))
      (node (ref "MOD1") (pin "14") (pinfunction "+3.3V_14") (pintype "bidirectional"))
    )
    (net (code "37") (name "Net-(R8-P$2)") (class "Default")
      (node (ref "LED1") (pin "C") (pinfunction "C_C") (pintype "passive"))
      (node (ref "R8") (pin "2") (pinfunction "P$2_2") (pintype "passive"))
    )
    (net (code "38") (name "Net-(R11-P$2)") (class "Default")
      (node (ref "LED4") (pin "C") (pinfunction "C_C") (pintype "passive"))
      (node (ref "R11") (pin "2") (pinfunction "P$2_2") (pintype "passive"))
    )
    (net (code "39") (name "Net-(R12-P$2)") (class "Default")
      (node (ref "LED5") (pin "C") (pinfunction "C_C") (pintype "passive"))
      (node (ref "R12") (pin "2") (pinfunction "P$2_2") (pintype "passive"))
    )
    (net (code "40") (name "Net-(R13-P$2)") (class "Default")
      (node (ref "LED6") (pin "C") (pinfunction "C_C") (pintype "passive"))
      (node (ref "R13") (pin "2") (pinfunction "P$2_2") (pintype "passive"))
    )
    (net (code "41") (name "Net-(R17-P$2)") (class "Default")
      (node (ref "LCD1") (pin "A") (pinfunction "A_A") (pintype "bidirectional"))
      (node (ref "R17") (pin "2") (pinfunction "P$2_2") (pintype "passive"))
    )
    (net (code "42") (name "Net-(R19-P$2)") (class "Default")
      (node (ref "R19") (pin "2") (pinfunction "P$2_2") (pintype "passive"))
      (node (ref "R20") (pin "2") (pinfunction "P$2_2") (pintype "passive"))
      (node (ref "R21") (pin "2") (pinfunction "P$2_2") (pintype "passive"))
      (node (ref "TP3") (pin "TP") (pinfunction "TP_TP") (pintype "input"))
    )
    (net (code "43") (name "Net-(R22-P$1)") (class "Default")
      (node (ref "R22") (pin "1") (pinfunction "P$1_1") (pintype "passive"))
      (node (ref "VR1") (pin "P$2") (pinfunction "S_P$2") (pintype "passive"))
    )
    (net (code "44") (name "Net-(R26-P$1)") (class "Default")
      (node (ref "R26") (pin "1") (pinfunction "P$1_1") (pintype "passive"))
      (node (ref "T2") (pin "1") (pinfunction "B_1") (pintype "passive"))
    )
    (net (code "45") (name "Net-(R27-P$1)") (class "Default")
      (node (ref "D2") (pin "K") (pinfunction "K_K") (pintype "passive"))
      (node (ref "D3") (pin "K") (pinfunction "K_K") (pintype "passive"))
      (node (ref "R27") (pin "1") (pinfunction "P$1_1") (pintype "passive"))
      (node (ref "R29") (pin "1") (pinfunction "P$1_1") (pintype "passive"))
      (node (ref "T3") (pin "E") (pinfunction "S_E") (pintype "passive"))
    )
    (net (code "46") (name "Net-(R29-P$2)") (class "Default")
      (node (ref "R29") (pin "2") (pinfunction "P$2_2") (pintype "passive"))
      (node (ref "T2") (pin "3") (pinfunction "C_3") (pintype "passive"))
      (node (ref "T3") (pin "B") (pinfunction "G_B") (pintype "passive"))
    )
    (net (code "47") (name "Net-(T3-D)") (class "Default")
      (node (ref "SW3") (pin "2") (pinfunction "2_2") (pintype "bidirectional"))
      (node (ref "T3") (pin "C") (pinfunction "D_C") (pintype "passive"))
    )
    (net (code "48") (name "PWM0-RED") (class "Default")
      (node (ref "R11") (pin "1") (pinfunction "P$1_1") (pintype "passive"))
      (node (ref "SKT1") (pin "21") (pinfunction "PWM0_21") (pintype "bidirectional"))
      (node (ref "SKT1") (pin "P$61") (pinfunction "P$61_P$61") (pintype "bidirectional"))
    )
    (net (code "49") (name "PWM1-BLUE") (class "Default")
      (node (ref "R12") (pin "1") (pinfunction "P$1_1") (pintype "passive"))
      (node (ref "SKT1") (pin "22") (pinfunction "PWM1_22") (pintype "bidirectional"))
      (node (ref "SKT1") (pin "P$62") (pinfunction "P$62_P$62") (pintype "bidirectional"))
    )
    (net (code "50") (name "PWM2-GREEN") (class "Default")
      (node (ref "R13") (pin "1") (pinfunction "P$1_1") (pintype "passive"))
      (node (ref "SKT1") (pin "23") (pinfunction "PWM2_23") (pintype "bidirectional"))
      (node (ref "SKT1") (pin "P$63") (pinfunction "P$63_P$63") (pintype "bidirectional"))
    )
    (net (code "51") (name "RX1") (class "Default")
      (node (ref "CON2") (pin "1") (pinfunction "RX/SCL_1") (pintype "bidirectional"))
      (node (ref "R23") (pin "2") (pinfunction "P$2_2") (pintype "passive"))
      (node (ref "SKT1") (pin "10") (pinfunction "RX1_10") (pintype "bidirectional"))
      (node (ref "SKT1") (pin "P$50") (pinfunction "P$50_P$50") (pintype "bidirectional"))
    )
    (net (code "52") (name "RX2") (class "Default")
      (node (ref "CON6") (pin "1") (pinfunction "RX/SCL_1") (pintype "bidirectional"))
      (node (ref "R18") (pin "2") (pinfunction "P$2_2") (pintype "passive"))
      (node (ref "SKT1") (pin "31") (pinfunction "RX2_31") (pintype "bidirectional"))
      (node (ref "SKT1") (pin "P$71") (pinfunction "P$71_P$71") (pintype "bidirectional"))
    )
    (net (code "53") (name "SCK1") (class "Default")
      (node (ref "CON1") (pin "1") (pinfunction "SCK_1") (pintype "bidirectional"))
      (node (ref "CON10") (pin "5") (pinfunction "SCK_5") (pintype "bidirectional"))
      (node (ref "LCD1") (pin "P$14") (pinfunction "SCL_P$14") (pintype "bidirectional"))
      (node (ref "SKT1") (pin "15") (pinfunction "SCK1_15") (pintype "bidirectional"))
      (node (ref "SKT1") (pin "P$55") (pinfunction "P$55_P$55") (pintype "bidirectional"))
    )
    (net (code "54") (name "SCK2") (class "Default")
      (node (ref "CON7") (pin "1") (pinfunction "SCK_1") (pintype "bidirectional"))
      (node (ref "SKT1") (pin "26") (pinfunction "SCK2_26") (pintype "bidirectional"))
      (node (ref "SKT1") (pin "P$66") (pinfunction "P$66_P$66") (pintype "bidirectional"))
    )
    (net (code "55") (name "SCL") (class "Default")
      (node (ref "IC4") (pin "2") (pinfunction "SCL_2") (pintype "bidirectional"))
      (node (ref "IC5") (pin "6") (pinfunction "SCL_6") (pintype "bidirectional"))
      (node (ref "JP4") (pin "4") (pinfunction "4_4") (pintype "passive"))
      (node (ref "R15") (pin "1") (pinfunction "P$1_1") (pintype "passive"))
      (node (ref "R7") (pin "1") (pinfunction "P$1_1") (pintype "passive"))
    )
    (net (code "56") (name "SCL1") (class "Default")
      (node (ref "CON5") (pin "1") (pinfunction "RX/SCL_1") (pintype "bidirectional"))
      (node (ref "JP4") (pin "2") (pinfunction "2_2") (pintype "passive"))
      (node (ref "SKT1") (pin "12") (pinfunction "SCL1_12") (pintype "bidirectional"))
      (node (ref "SKT1") (pin "P$52") (pinfunction "P$52_P$52") (pintype "bidirectional"))
    )
    (net (code "57") (name "SCL2") (class "Default")
      (node (ref "CON8") (pin "1") (pinfunction "RX/SCL_1") (pintype "bidirectional"))
      (node (ref "JP4") (pin "6") (pinfunction "6_6") (pintype "passive"))
      (node (ref "SKT1") (pin "29") (pinfunction "SCL2_29") (pintype "bidirectional"))
      (node (ref "SKT1") (pin "P$69") (pinfunction "P$69_P$69") (pintype "bidirectional"))
    )
    (net (code "58") (name "SDA") (class "Default")
      (node (ref "IC4") (pin "1") (pinfunction "SDA_1") (pintype "bidirectional"))
      (node (ref "IC5") (pin "5") (pinfunction "SDA_5") (pintype "bidirectional"))
      (node (ref "JP4") (pin "3") (pinfunction "3_3") (pintype "passive"))
      (node (ref "R14") (pin "1") (pinfunction "P$1_1") (pintype "passive"))
      (node (ref "R6") (pin "1") (pinfunction "P$1_1") (pintype "passive"))
    )
    (net (code "59") (name "SDA1") (class "Default")
      (node (ref "CON5") (pin "2") (pinfunction "TX/SDA_2") (pintype "bidirectional"))
      (node (ref "JP4") (pin "1") (pinfunction "1_1") (pintype "passive"))
      (node (ref "SKT1") (pin "11") (pinfunction "SDA1_11") (pintype "bidirectional"))
      (node (ref "SKT1") (pin "P$51") (pinfunction "P$51_P$51") (pintype "bidirectional"))
    )
    (net (code "60") (name "SDA2") (class "Default")
      (node (ref "CON8") (pin "2") (pinfunction "TX/SDA_2") (pintype "bidirectional"))
      (node (ref "JP4") (pin "5") (pinfunction "5_5") (pintype "passive"))
      (node (ref "SKT1") (pin "30") (pinfunction "SDA2_30") (pintype "bidirectional"))
      (node (ref "SKT1") (pin "P$70") (pinfunction "P$70_P$70") (pintype "bidirectional"))
    )
    (net (code "61") (name "TGT_CTS") (class "Default")
      (node (ref "MOD1") (pin "8") (pinfunction "TGT_CTS_8") (pintype "bidirectional"))
      (node (ref "SKT1") (pin "39") (pinfunction "TGT_CTS_39") (pintype "bidirectional"))
      (node (ref "SKT1") (pin "P$79") (pinfunction "P$79_P$79") (pintype "bidirectional"))
    )
    (net (code "62") (name "TGT_NRESET") (class "Default")
      (node (ref "MOD1") (pin "7") (pinfunction "~{RESET}_7") (pintype "bidirectional"))
      (node (ref "SKT1") (pin "6") (pinfunction "NRESET_6") (pintype "bidirectional"))
      (node (ref "SKT1") (pin "P$46") (pinfunction "P$46_P$46") (pintype "bidirectional"))
    )
    (net (code "63") (name "TGT_RTS") (class "Default")
      (node (ref "MOD1") (pin "6") (pinfunction "TGT_RTS_6") (pintype "bidirectional"))
      (node (ref "SKT1") (pin "38") (pinfunction "TGT_RTS_38") (pintype "bidirectional"))
      (node (ref "SKT1") (pin "P$78") (pinfunction "P$78_P$78") (pintype "bidirectional"))
    )
    (net (code "64") (name "TGT_RX") (class "Default")
      (node (ref "MOD1") (pin "11") (pinfunction "TGT_RX_11") (pintype "bidirectional"))
      (node (ref "SKT1") (pin "8") (pinfunction "TGT_RX_8") (pintype "bidirectional"))
      (node (ref "SKT1") (pin "P$48") (pinfunction "P$48_P$48") (pintype "bidirectional"))
    )
    (net (code "65") (name "TGT_SWCLK") (class "Default")
      (node (ref "MOD1") (pin "3") (pinfunction "SWCLK_3") (pintype "bidirectional"))
      (node (ref "SKT1") (pin "5") (pinfunction "SWCLK_5") (pintype "bidirectional"))
      (node (ref "SKT1") (pin "P$45") (pinfunction "P$45_P$45") (pintype "bidirectional"))
    )
    (net (code "66") (name "TGT_SWDIO") (class "Default")
      (node (ref "MOD1") (pin "5") (pinfunction "SWDIO_5") (pintype "bidirectional"))
      (node (ref "SKT1") (pin "4") (pinfunction "SWDIO_4") (pintype "bidirectional"))
      (node (ref "SKT1") (pin "P$44") (pinfunction "P$44_P$44") (pintype "bidirectional"))
    )
    (net (code "67") (name "TGT_TX") (class "Default")
      (node (ref "MOD1") (pin "9") (pinfunction "TGT_TX_9") (pintype "bidirectional"))
      (node (ref "SKT1") (pin "7") (pinfunction "TGT_TX_7") (pintype "bidirectional"))
      (node (ref "SKT1") (pin "P$47") (pinfunction "P$47_P$47") (pintype "bidirectional"))
    )
    (net (code "68") (name "TX1") (class "Default")
      (node (ref "CON2") (pin "2") (pinfunction "TX/SDA_2") (pintype "bidirectional"))
      (node (ref "R23") (pin "1") (pinfunction "P$1_1") (pintype "passive"))
      (node (ref "SKT1") (pin "9") (pinfunction "TX1_9") (pintype "bidirectional"))
      (node (ref "SKT1") (pin "P$49") (pinfunction "P$49_P$49") (pintype "bidirectional"))
    )
    (net (code "69") (name "TX2") (class "Default")
      (node (ref "CON6") (pin "2") (pinfunction "TX/SDA_2") (pintype "bidirectional"))
      (node (ref "R18") (pin "1") (pinfunction "P$1_1") (pintype "passive"))
      (node (ref "SKT1") (pin "32") (pinfunction "TX2_32") (pintype "bidirectional"))
      (node (ref "SKT1") (pin "P$72") (pinfunction "P$72_P$72") (pintype "bidirectional"))
    )
    (net (code "70") (name "VCC_GROVE") (class "Default")
      (node (ref "CON2") (pin "3") (pinfunction "VCC_3") (pintype "bidirectional"))
      (node (ref "CON3") (pin "3") (pinfunction "VCC_3") (pintype "bidirectional"))
      (node (ref "CON4") (pin "3") (pinfunction "VCC_3") (pintype "bidirectional"))
      (node (ref "CON5") (pin "3") (pinfunction "VCC_3") (pintype "bidirectional"))
      (node (ref "CON6") (pin "3") (pinfunction "VCC_3") (pintype "bidirectional"))
      (node (ref "CON8") (pin "3") (pinfunction "VCC_3") (pintype "bidirectional"))
      (node (ref "JP1") (pin "2") (pinfunction "2_2") (pintype "passive"))
    )
    (net (code "71") (name "unconnected-(CON10-NC-Pad1)") (class "Default")
      (node (ref "CON10") (pin "1") (pinfunction "NC_1") (pintype "bidirectional"))
    )
    (net (code "72") (name "unconnected-(CON10-NC-Pad8)") (class "Default")
      (node (ref "CON10") (pin "8") (pinfunction "NC_8") (pintype "bidirectional"))
    )
    (net (code "73") (name "unconnected-(CON10-PadCD)") (class "Default")
      (node (ref "CON10") (pin "CD") (pinfunction "CD_CD") (pintype "bidirectional"))
    )
    (net (code "74") (name "unconnected-(CON12-GNDBREAK-Pad2)") (class "Default")
      (node (ref "CON12") (pin "2") (pinfunction "GNDBREAK_2") (pintype "bidirectional"))
    )
    (net (code "75") (name "unconnected-(IC2-K-Pad4)") (class "Default")
      (node (ref "IC2") (pin "4") (pinfunction "K_4") (pintype "passive"))
    )
    (net (code "76") (name "unconnected-(IC4-OS-Pad3)") (class "Default")
      (node (ref "IC4") (pin "3") (pinfunction "OS_3") (pintype "bidirectional"))
    )
    (net (code "77") (name "unconnected-(IC5-WP-Pad7)") (class "Default")
      (node (ref "IC5") (pin "7") (pinfunction "WP_7") (pintype "bidirectional"))
    )
    (net (code "78") (name "unconnected-(MOD1-SWO-Pad4)") (class "Default")
      (node (ref "MOD1") (pin "4") (pinfunction "SWO_4") (pintype "bidirectional"))
    )
    (net (code "79") (name "unconnected-(MOD1-VDET-Pad2)") (class "Default")
      (node (ref "MOD1") (pin "2") (pinfunction "VDET_2") (pintype "bidirectional"))
    )
    (net (code "80") (name "unconnected-(SW3-Pad3)") (class "Default")
      (node (ref "SW3") (pin "3") (pinfunction "3_3") (pintype "bidirectional"))
    )
    (net (code "81") (name "unconnected-(SW3-Pad5)") (class "Default")
      (node (ref "SW3") (pin "5") (pinfunction "5_5") (pintype "bidirectional"))
    )
    (net (code "82") (name "unconnected-(SW3-Pad6)") (class "Default")
      (node (ref "SW3") (pin "6") (pinfunction "6_6") (pintype "bidirectional"))
    )
    (net (code "83") (name "unconnected-(SW3-Pad7)") (class "Default")
      (node (ref "SW3") (pin "7") (pinfunction "7_7") (pintype "bidirectional"))
    )
    (net (code "84") (name "~{PWR_OFF}") (class "Default")
      (node (ref "JP3") (pin "2") (pinfunction "2_2") (pintype "passive"))
      (node (ref "MOD1") (pin "13") (pinfunction "IF_GPIO_13") (pintype "bidirectional"))
      (node (ref "R26") (pin "2") (pinfunction "P$2_2") (pintype "passive"))
      (node (ref "R27") (pin "2") (pinfunction "P$2_2") (pintype "passive"))
    )
  )
)
